# buttons_and_leds.net
KiCad netlist of a schematic drawn in Altium Designer
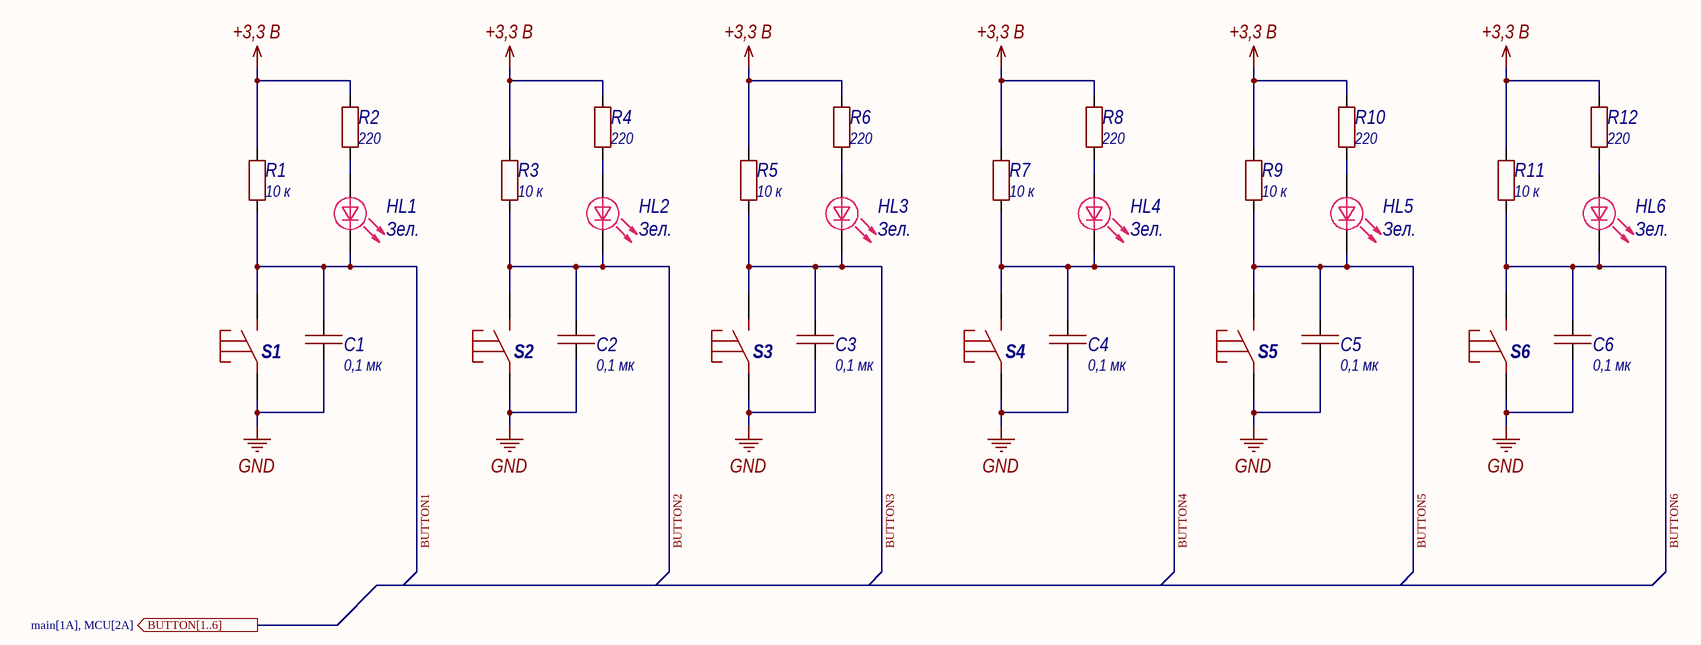
[diagram p0: buttons_and_leds.SchDoc]

(export (version "E")
  (design (tool "Eeschema 10.0.6"))
  (components
    (comp (ref "C1")
      (value "0,1 мк")
      (footprint "0603C")
      (description "Конденсатор 0603C ёмкостью 0,1 мк 10%, 50 В, X7R")
      (fields (field (name "PART NUMBER") "Capacitor_0,1u_10_50V_X7R_0603C") (field (name "TOLERANCE") "10%"))
      (libsource (lib "Hydrolib") (part "Capacitor"))
    )
    (comp (ref "C2")
      (value "0,1 мк")
      (footprint "0603C")
      (description "Конденсатор 0603C ёмкостью 0,1 мк 10%, 50 В, X7R")
      (fields (field (name "PART NUMBER") "Capacitor_0,1u_10_50V_X7R_0603C") (field (name "TOLERANCE") "10%"))
      (libsource (lib "Hydrolib") (part "Capacitor"))
    )
    (comp (ref "C3")
      (value "0,1 мк")
      (footprint "0603C")
      (description "Конденсатор 0603C ёмкостью 0,1 мк 10%, 50 В, X7R")
      (fields (field (name "PART NUMBER") "Capacitor_0,1u_10_50V_X7R_0603C") (field (name "TOLERANCE") "10%"))
      (libsource (lib "Hydrolib") (part "Capacitor"))
    )
    (comp (ref "C4")
      (value "0,1 мк")
      (footprint "0603C")
      (description "Конденсатор 0603C ёмкостью 0,1 мк 10%, 50 В, X7R")
      (fields (field (name "PART NUMBER") "Capacitor_0,1u_10_50V_X7R_0603C") (field (name "TOLERANCE") "10%"))
      (libsource (lib "Hydrolib") (part "Capacitor"))
    )
    (comp (ref "C5")
      (value "0,1 мк")
      (footprint "0603C")
      (description "Конденсатор 0603C ёмкостью 0,1 мк 10%, 50 В, X7R")
      (fields (field (name "PART NUMBER") "Capacitor_0,1u_10_50V_X7R_0603C") (field (name "TOLERANCE") "10%"))
      (libsource (lib "Hydrolib") (part "Capacitor"))
    )
    (comp (ref "C6")
      (value "0,1 мк")
      (footprint "0603C")
      (description "Конденсатор 0603C ёмкостью 0,1 мк 10%, 50 В, X7R")
      (fields (field (name "PART NUMBER") "Capacitor_0,1u_10_50V_X7R_0603C") (field (name "TOLERANCE") "10%"))
      (libsource (lib "Hydrolib") (part "Capacitor"))
    )
    (comp (ref "HL1")
      (value "LED")
      (footprint "0805D")
      (description "Светодиод")
      (fields (field (name "COLOR") "Зел."))
      (libsource (lib "Hydrolib") (part "LED"))
    )
    (comp (ref "HL2")
      (value "LED")
      (footprint "0805D")
      (description "Светодиод")
      (fields (field (name "COLOR") "Зел."))
      (libsource (lib "Hydrolib") (part "LED"))
    )
    (comp (ref "HL3")
      (value "LED")
      (footprint "0805D")
      (description "Светодиод")
      (fields (field (name "COLOR") "Зел."))
      (libsource (lib "Hydrolib") (part "LED"))
    )
    (comp (ref "HL4")
      (value "LED")
      (footprint "0805D")
      (description "Светодиод")
      (fields (field (name "COLOR") "Зел."))
      (libsource (lib "Hydrolib") (part "LED"))
    )
    (comp (ref "HL5")
      (value "LED")
      (footprint "0805D")
      (description "Светодиод")
      (fields (field (name "COLOR") "Зел."))
      (libsource (lib "Hydrolib") (part "LED"))
    )
    (comp (ref "HL6")
      (value "LED")
      (footprint "0805D")
      (description "Светодиод")
      (fields (field (name "COLOR") "Зел."))
      (libsource (lib "Hydrolib") (part "LED"))
    )
    (comp (ref "R1")
      (value "10 к")
      (footprint "0603R")
      (description "Резистор номиналом 10 кОм 1%")
      (fields (field (name "PART NUMBER") "Resistor_10k_1_0603") (field (name "TOLERANCE") "1%"))
      (libsource (lib "Hydrolib") (part "Resistor"))
    )
    (comp (ref "R2")
      (value "220")
      (footprint "0603R")
      (description "Резистор номиналом 220 Ом 1%")
      (fields (field (name "PART NUMBER") "Resistor_220_1_0603") (field (name "TOLERANCE") "1%"))
      (libsource (lib "") (part "Resistor_1"))
    )
    (comp (ref "R3")
      (value "10 к")
      (footprint "0603R")
      (description "Резистор номиналом 10 кОм 1%")
      (fields (field (name "PART NUMBER") "Resistor_10k_1_0603") (field (name "TOLERANCE") "1%"))
      (libsource (lib "Hydrolib") (part "Resistor"))
    )
    (comp (ref "R4")
      (value "220")
      (footprint "0603R")
      (description "Резистор номиналом 220 Ом 1%")
      (fields (field (name "PART NUMBER") "Resistor_220_1_0603") (field (name "TOLERANCE") "1%"))
      (libsource (lib "") (part "Resistor_1"))
    )
    (comp (ref "R5")
      (value "10 к")
      (footprint "0603R")
      (description "Резистор номиналом 10 кОм 1%")
      (fields (field (name "PART NUMBER") "Resistor_10k_1_0603") (field (name "TOLERANCE") "1%"))
      (libsource (lib "Hydrolib") (part "Resistor"))
    )
    (comp (ref "R6")
      (value "220")
      (footprint "0603R")
      (description "Резистор номиналом 220 Ом 1%")
      (fields (field (name "PART NUMBER") "Resistor_220_1_0603") (field (name "TOLERANCE") "1%"))
      (libsource (lib "") (part "Resistor_1"))
    )
    (comp (ref "R7")
      (value "10 к")
      (footprint "0603R")
      (description "Резистор номиналом 10 кОм 1%")
      (fields (field (name "PART NUMBER") "Resistor_10k_1_0603") (field (name "TOLERANCE") "1%"))
      (libsource (lib "Hydrolib") (part "Resistor"))
    )
    (comp (ref "R8")
      (value "220")
      (footprint "0603R")
      (description "Резистор номиналом 220 Ом 1%")
      (fields (field (name "PART NUMBER") "Resistor_220_1_0603") (field (name "TOLERANCE") "1%"))
      (libsource (lib "") (part "Resistor_1"))
    )
    (comp (ref "R9")
      (value "10 к")
      (footprint "0603R")
      (description "Резистор номиналом 10 кОм 1%")
      (fields (field (name "PART NUMBER") "Resistor_10k_1_0603") (field (name "TOLERANCE") "1%"))
      (libsource (lib "Hydrolib") (part "Resistor"))
    )
    (comp (ref "R10")
      (value "220")
      (footprint "0603R")
      (description "Резистор номиналом 220 Ом 1%")
      (fields (field (name "PART NUMBER") "Resistor_220_1_0603") (field (name "TOLERANCE") "1%"))
      (libsource (lib "") (part "Resistor_1"))
    )
    (comp (ref "R11")
      (value "10 к")
      (footprint "0603R")
      (description "Резистор номиналом 10 кОм 1%")
      (fields (field (name "PART NUMBER") "Resistor_10k_1_0603") (field (name "TOLERANCE") "1%"))
      (libsource (lib "Hydrolib") (part "Resistor"))
    )
    (comp (ref "R12")
      (value "220")
      (footprint "0603R")
      (description "Резистор номиналом 220 Ом 1%")
      (fields (field (name "PART NUMBER") "Resistor_220_1_0603") (field (name "TOLERANCE") "1%"))
      (libsource (lib "") (part "Resistor_1"))
    )
    (comp (ref "S1")
      (value "Button_DIP_12x12")
      (footprint "Button_DIP_12x12")
      (description "Тактовая кнопка, DIP 12 x 12 мм")
      (libsource (lib "Hydrolib") (part "Tact_button"))
    )
    (comp (ref "S2")
      (value "Button_DIP_12x12")
      (footprint "Button_DIP_12x12")
      (description "Тактовая кнопка, DIP 12 x 12 мм")
      (libsource (lib "Hydrolib") (part "Tact_button"))
    )
    (comp (ref "S3")
      (value "Button_DIP_12x12")
      (footprint "Button_DIP_12x12")
      (description "Тактовая кнопка, DIP 12 x 12 мм")
      (libsource (lib "Hydrolib") (part "Tact_button"))
    )
    (comp (ref "S4")
      (value "Button_DIP_12x12")
      (footprint "Button_DIP_12x12")
      (description "Тактовая кнопка, DIP 12 x 12 мм")
      (libsource (lib "Hydrolib") (part "Tact_button"))
    )
    (comp (ref "S5")
      (value "Button_DIP_12x12")
      (footprint "Button_DIP_12x12")
      (description "Тактовая кнопка, DIP 12 x 12 мм")
      (libsource (lib "Hydrolib") (part "Tact_button"))
    )
    (comp (ref "S6")
      (value "Button_DIP_12x12")
      (footprint "Button_DIP_12x12")
      (description "Тактовая кнопка, DIP 12 x 12 мм")
      (libsource (lib "Hydrolib") (part "Tact_button"))
    )
  )
  (nets
    (net (code "1") (name "+3,3 В") (class "Default")
      (node (ref "R1") (pin "2") (pinfunction "2_2") (pintype "passive"))
      (node (ref "R10") (pin "1") (pinfunction "1_1") (pintype "passive"))
      (node (ref "R11") (pin "2") (pinfunction "2_2") (pintype "passive"))
      (node (ref "R12") (pin "1") (pinfunction "1_1") (pintype "passive"))
      (node (ref "R2") (pin "1") (pinfunction "1_1") (pintype "passive"))
      (node (ref "R3") (pin "2") (pinfunction "2_2") (pintype "passive"))
      (node (ref "R4") (pin "1") (pinfunction "1_1") (pintype "passive"))
      (node (ref "R5") (pin "2") (pinfunction "2_2") (pintype "passive"))
      (node (ref "R6") (pin "1") (pinfunction "1_1") (pintype "passive"))
      (node (ref "R7") (pin "2") (pinfunction "2_2") (pintype "passive"))
      (node (ref "R8") (pin "1") (pinfunction "1_1") (pintype "passive"))
      (node (ref "R9") (pin "2") (pinfunction "2_2") (pintype "passive"))
    )
    (net (code "2") (name "/BUTTON1") (class "Default")
      (node (ref "C1") (pin "2") (pinfunction "2_2") (pintype "passive"))
      (node (ref "HL1") (pin "2") (pinfunction "2_2") (pintype "passive"))
      (node (ref "R1") (pin "1") (pinfunction "1_1") (pintype "passive"))
      (node (ref "S1") (pin "2") (pinfunction "2_2") (pintype "passive"))
    )
    (net (code "3") (name "/BUTTON2") (class "Default")
      (node (ref "C2") (pin "2") (pinfunction "2_2") (pintype "passive"))
      (node (ref "HL2") (pin "2") (pinfunction "2_2") (pintype "passive"))
      (node (ref "R3") (pin "1") (pinfunction "1_1") (pintype "passive"))
      (node (ref "S2") (pin "2") (pinfunction "2_2") (pintype "passive"))
    )
    (net (code "4") (name "/BUTTON3") (class "Default")
      (node (ref "C3") (pin "2") (pinfunction "2_2") (pintype "passive"))
      (node (ref "HL3") (pin "2") (pinfunction "2_2") (pintype "passive"))
      (node (ref "R5") (pin "1") (pinfunction "1_1") (pintype "passive"))
      (node (ref "S3") (pin "2") (pinfunction "2_2") (pintype "passive"))
    )
    (net (code "5") (name "/BUTTON4") (class "Default")
      (node (ref "C4") (pin "2") (pinfunction "2_2") (pintype "passive"))
      (node (ref "HL4") (pin "2") (pinfunction "2_2") (pintype "passive"))
      (node (ref "R7") (pin "1") (pinfunction "1_1") (pintype "passive"))
      (node (ref "S4") (pin "2") (pinfunction "2_2") (pintype "passive"))
    )
    (net (code "6") (name "/BUTTON5") (class "Default")
      (node (ref "C5") (pin "2") (pinfunction "2_2") (pintype "passive"))
      (node (ref "HL5") (pin "2") (pinfunction "2_2") (pintype "passive"))
      (node (ref "R9") (pin "1") (pinfunction "1_1") (pintype "passive"))
      (node (ref "S5") (pin "2") (pinfunction "2_2") (pintype "passive"))
    )
    (net (code "7") (name "/BUTTON6") (class "Default")
      (node (ref "C6") (pin "2") (pinfunction "2_2") (pintype "passive"))
      (node (ref "HL6") (pin "2") (pinfunction "2_2") (pintype "passive"))
      (node (ref "R11") (pin "1") (pinfunction "1_1") (pintype "passive"))
      (node (ref "S6") (pin "2") (pinfunction "2_2") (pintype "passive"))
    )
    (net (code "9") (name "GND") (class "Default")
      (node (ref "C1") (pin "1") (pinfunction "1_1") (pintype "passive"))
      (node (ref "C2") (pin "1") (pinfunction "1_1") (pintype "passive"))
      (node (ref "C3") (pin "1") (pinfunction "1_1") (pintype "passive"))
      (node (ref "C4") (pin "1") (pinfunction "1_1") (pintype "passive"))
      (node (ref "C5") (pin "1") (pinfunction "1_1") (pintype "passive"))
      (node (ref "C6") (pin "1") (pinfunction "1_1") (pintype "passive"))
      (node (ref "S1") (pin "1") (pinfunction "1_1") (pintype "passive"))
      (node (ref "S2") (pin "1") (pinfunction "1_1") (pintype "passive"))
      (node (ref "S3") (pin "1") (pinfunction "1_1") (pintype "passive"))
      (node (ref "S4") (pin "1") (pinfunction "1_1") (pintype "passive"))
      (node (ref "S5") (pin "1") (pinfunction "1_1") (pintype "passive"))
      (node (ref "S6") (pin "1") (pinfunction "1_1") (pintype "passive"))
    )
    (net (code "10") (name "Net-(HL1-Pad1)") (class "Default")
      (node (ref "HL1") (pin "1") (pinfunction "1_1") (pintype "passive"))
      (node (ref "R2") (pin "2") (pinfunction "2_2") (pintype "passive"))
    )
    (net (code "11") (name "Net-(HL2-Pad1)") (class "Default")
      (node (ref "HL2") (pin "1") (pinfunction "1_1") (pintype "passive"))
      (node (ref "R4") (pin "2") (pinfunction "2_2") (pintype "passive"))
    )
    (net (code "12") (name "Net-(HL3-Pad1)") (class "Default")
      (node (ref "HL3") (pin "1") (pinfunction "1_1") (pintype "passive"))
      (node (ref "R6") (pin "2") (pinfunction "2_2") (pintype "passive"))
    )
    (net (code "13") (name "Net-(HL4-Pad1)") (class "Default")
      (node (ref "HL4") (pin "1") (pinfunction "1_1") (pintype "passive"))
      (node (ref "R8") (pin "2") (pinfunction "2_2") (pintype "passive"))
    )
    (net (code "14") (name "Net-(HL5-Pad1)") (class "Default")
      (node (ref "HL5") (pin "1") (pinfunction "1_1") (pintype "passive"))
      (node (ref "R10") (pin "2") (pinfunction "2_2") (pintype "passive"))
    )
    (net (code "15") (name "Net-(HL6-Pad1)") (class "Default")
      (node (ref "HL6") (pin "1") (pinfunction "1_1") (pintype "passive"))
      (node (ref "R12") (pin "2") (pinfunction "2_2") (pintype "passive"))
    )
  )
)
